# ShiftRegisters.net
KiCad netlist of a schematic drawn in Altium Designer
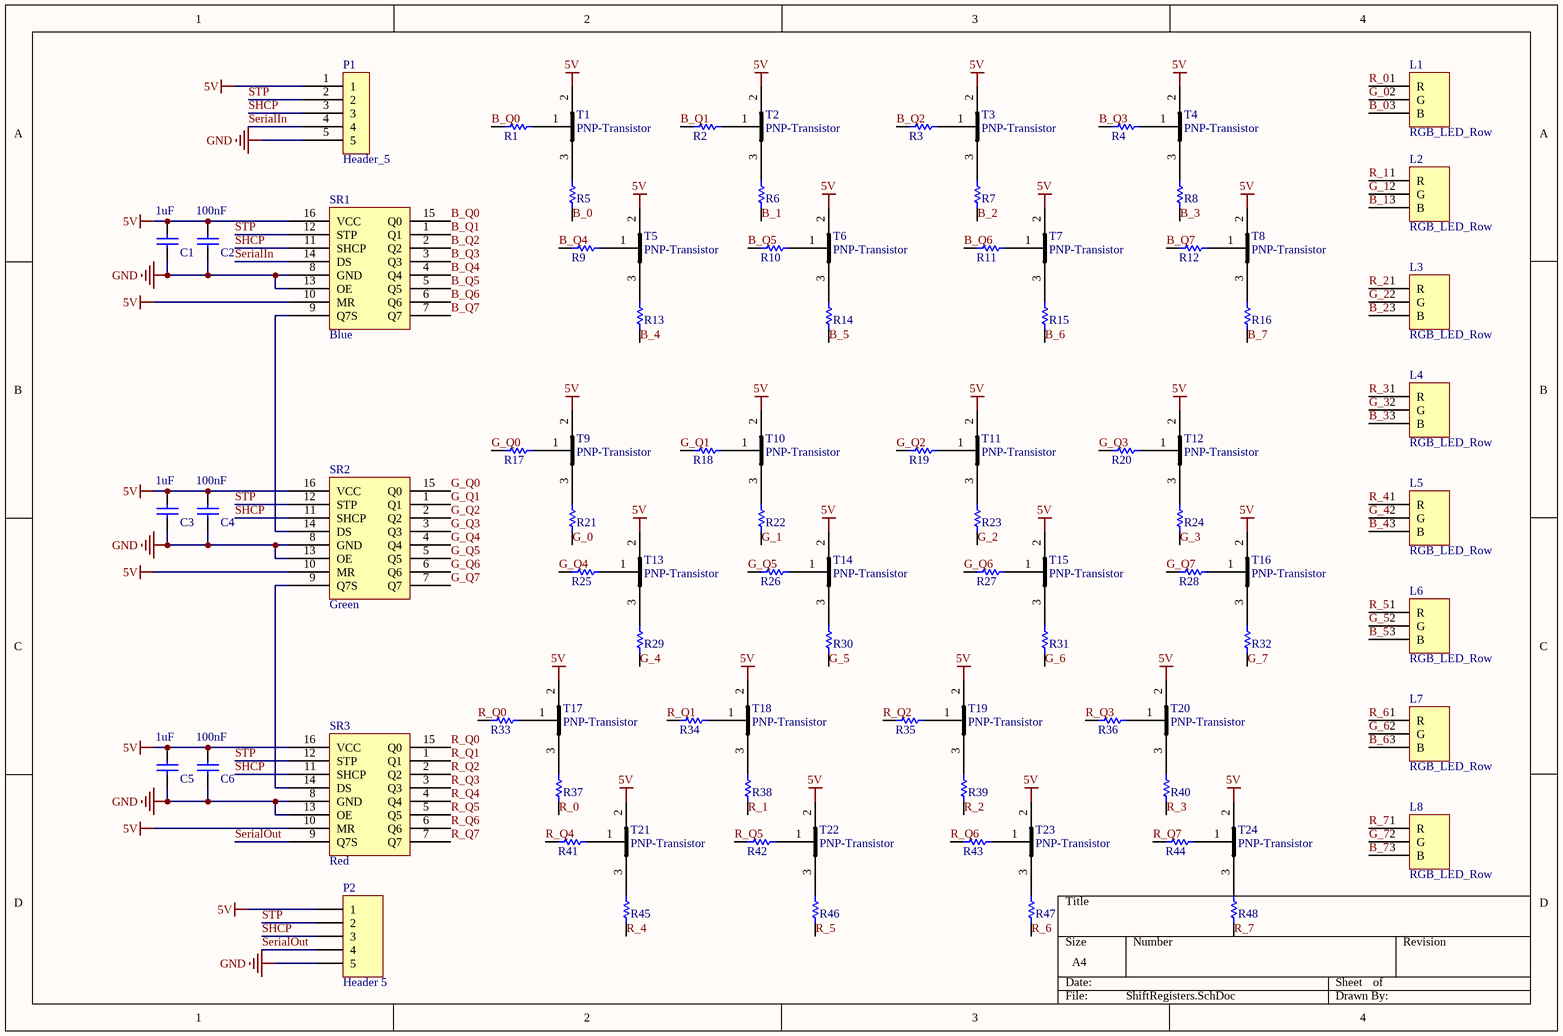
[diagram p0: ShiftRegisters.SchDoc]

(export (version "E")
  (design (tool "Eeschema 10.0.6"))
  (components
    (comp (ref "C1")
      (value "1uF")
      (footprint "CAPC1206(3216)190_L")
      (description "CAP 100nF 16V Â±1% 1206 (3216 Metric) Thickness 1.9mm SMD")
      (fields (field (name "TOLERANCE") "Â±1%") (field (name "Comment") "CAP 100nF 16V 1206(3216)"))
      (libsource (lib "Altium Content Vault") (part "CAP"))
    )
    (comp (ref "C2")
      (value "100nF")
      (footprint "CAPC1206(3216)190_L")
      (description "CAP 100nF 16V Â±1% 1206 (3216 Metric) Thickness 1.9mm SMD")
      (fields (field (name "TOLERANCE") "Â±1%") (field (name "Comment") "CAP 100nF 16V 1206(3216)"))
      (libsource (lib "Altium Content Vault") (part "CAP"))
    )
    (comp (ref "C3")
      (value "1uF")
      (footprint "CAPC1206(3216)190_L")
      (description "CAP 100nF 16V Â±1% 1206 (3216 Metric) Thickness 1.9mm SMD")
      (fields (field (name "TOLERANCE") "Â±1%") (field (name "Comment") "CAP 100nF 16V 1206(3216)"))
      (libsource (lib "Altium Content Vault") (part "CAP"))
    )
    (comp (ref "C4")
      (value "100nF")
      (footprint "CAPC1206(3216)190_L")
      (description "CAP 100nF 16V Â±1% 1206 (3216 Metric) Thickness 1.9mm SMD")
      (fields (field (name "TOLERANCE") "Â±1%") (field (name "Comment") "CAP 100nF 16V 1206(3216)"))
      (libsource (lib "Altium Content Vault") (part "CAP"))
    )
    (comp (ref "C5")
      (value "1uF")
      (footprint "CAPC1206(3216)190_L")
      (description "CAP 100nF 16V Â±1% 1206 (3216 Metric) Thickness 1.9mm SMD")
      (fields (field (name "TOLERANCE") "Â±1%") (field (name "Comment") "CAP 100nF 16V 1206(3216)"))
      (libsource (lib "Altium Content Vault") (part "CAP"))
    )
    (comp (ref "C6")
      (value "100nF")
      (footprint "CAPC1206(3216)190_L")
      (description "CAP 100nF 16V Â±1% 1206 (3216 Metric) Thickness 1.9mm SMD")
      (fields (field (name "TOLERANCE") "Â±1%") (field (name "Comment") "CAP 100nF 16V 1206(3216)"))
      (libsource (lib "Altium Content Vault") (part "CAP"))
    )
    (comp (ref "L1")
      (value "RGB_LED_Row")
      (footprint "LED_Row")
      (libsource (lib "RGB-Cube") (part "RGB_LED_Row"))
    )
    (comp (ref "L2")
      (value "RGB_LED_Row")
      (footprint "LED_Row")
      (libsource (lib "RGB-Cube") (part "RGB_LED_Row"))
    )
    (comp (ref "L3")
      (value "RGB_LED_Row")
      (footprint "LED_Row")
      (libsource (lib "RGB-Cube") (part "RGB_LED_Row"))
    )
    (comp (ref "L4")
      (value "RGB_LED_Row")
      (footprint "LED_Row")
      (libsource (lib "RGB-Cube") (part "RGB_LED_Row"))
    )
    (comp (ref "L5")
      (value "RGB_LED_Row")
      (footprint "LED_Row")
      (libsource (lib "RGB-Cube") (part "RGB_LED_Row"))
    )
    (comp (ref "L6")
      (value "RGB_LED_Row")
      (footprint "LED_Row")
      (libsource (lib "RGB-Cube") (part "RGB_LED_Row"))
    )
    (comp (ref "L7")
      (value "RGB_LED_Row")
      (footprint "LED_Row")
      (libsource (lib "RGB-Cube") (part "RGB_LED_Row"))
    )
    (comp (ref "L8")
      (value "RGB_LED_Row")
      (footprint "LED_Row")
      (libsource (lib "RGB-Cube") (part "RGB_LED_Row"))
    )
    (comp (ref "P1")
      (value "Header_5")
      (footprint "PinHeader")
      (libsource (lib "RGB-Cube") (part "Header_5"))
    )
    (comp (ref "P2")
      (value "Header 5")
      (footprint "HDR1X5")
      (description "Header, 5-Pin")
      (fields (field (name "PUBLISHER") "Altium Limited"))
      (libsource (lib "Miscellaneous Connectors") (part "Header 5"))
    )
    (comp (ref "R1")
      (value "43k 5% 1206(3216)")
      (footprint "RESC1206(3216)_M")
      (description "43k 0.25W 5% 1206 (3216 Metric)  SMD")
      (fields (field (name "TOLERANCE") "5 %") (field (name "POWER") "0.25 W"))
      (libsource (lib "Altium Content Vault") (part "CMP-1014-00009-1"))
    )
    (comp (ref "R2")
      (value "43k 5% 1206(3216)")
      (footprint "RESC1206(3216)_M")
      (description "43k 0.25W 5% 1206 (3216 Metric)  SMD")
      (fields (field (name "TOLERANCE") "5 %") (field (name "POWER") "0.25 W"))
      (libsource (lib "Altium Content Vault") (part "CMP-1014-00009-1"))
    )
    (comp (ref "R3")
      (value "43k 5% 1206(3216)")
      (footprint "RESC1206(3216)_M")
      (description "43k 0.25W 5% 1206 (3216 Metric)  SMD")
      (fields (field (name "TOLERANCE") "5 %") (field (name "POWER") "0.25 W"))
      (libsource (lib "Altium Content Vault") (part "CMP-1014-00009-1"))
    )
    (comp (ref "R4")
      (value "43k 5% 1206(3216)")
      (footprint "RESC1206(3216)_M")
      (description "43k 0.25W 5% 1206 (3216 Metric)  SMD")
      (fields (field (name "TOLERANCE") "5 %") (field (name "POWER") "0.25 W"))
      (libsource (lib "Altium Content Vault") (part "CMP-1014-00009-1"))
    )
    (comp (ref "R5")
      (value "2R 5% 1206(3216)")
      (footprint "RESC1206(3216)_M")
      (description "2R 0.25W 5% 1206 (3216 Metric)  SMD")
      (fields (field (name "TOLERANCE") "5 %") (field (name "POWER") "0.25 W"))
      (libsource (lib "Altium Content Vault") (part "CMP-1014-00009-1"))
    )
    (comp (ref "R6")
      (value "2R 5% 1206(3216)")
      (footprint "RESC1206(3216)_M")
      (description "2R 0.25W 5% 1206 (3216 Metric)  SMD")
      (fields (field (name "TOLERANCE") "5 %") (field (name "POWER") "0.25 W"))
      (libsource (lib "Altium Content Vault") (part "CMP-1014-00009-1"))
    )
    (comp (ref "R7")
      (value "2R 5% 1206(3216)")
      (footprint "RESC1206(3216)_M")
      (description "2R 0.25W 5% 1206 (3216 Metric)  SMD")
      (fields (field (name "TOLERANCE") "5 %") (field (name "POWER") "0.25 W"))
      (libsource (lib "Altium Content Vault") (part "CMP-1014-00009-1"))
    )
    (comp (ref "R8")
      (value "2R 5% 1206(3216)")
      (footprint "RESC1206(3216)_M")
      (description "2R 0.25W 5% 1206 (3216 Metric)  SMD")
      (fields (field (name "TOLERANCE") "5 %") (field (name "POWER") "0.25 W"))
      (libsource (lib "Altium Content Vault") (part "CMP-1014-00009-1"))
    )
    (comp (ref "R9")
      (value "43k 5% 1206(3216)")
      (footprint "RESC1206(3216)_M")
      (description "43k 0.25W 5% 1206 (3216 Metric)  SMD")
      (fields (field (name "TOLERANCE") "5 %") (field (name "POWER") "0.25 W"))
      (libsource (lib "Altium Content Vault") (part "CMP-1014-00009-1"))
    )
    (comp (ref "R10")
      (value "43k 5% 1206(3216)")
      (footprint "RESC1206(3216)_M")
      (description "43k 0.25W 5% 1206 (3216 Metric)  SMD")
      (fields (field (name "TOLERANCE") "5 %") (field (name "POWER") "0.25 W"))
      (libsource (lib "Altium Content Vault") (part "CMP-1014-00009-1"))
    )
    (comp (ref "R11")
      (value "43k 5% 1206(3216)")
      (footprint "RESC1206(3216)_M")
      (description "43k 0.25W 5% 1206 (3216 Metric)  SMD")
      (fields (field (name "TOLERANCE") "5 %") (field (name "POWER") "0.25 W"))
      (libsource (lib "Altium Content Vault") (part "CMP-1014-00009-1"))
    )
    (comp (ref "R12")
      (value "43k 5% 1206(3216)")
      (footprint "RESC1206(3216)_M")
      (description "43k 0.25W 5% 1206 (3216 Metric)  SMD")
      (fields (field (name "TOLERANCE") "5 %") (field (name "POWER") "0.25 W"))
      (libsource (lib "Altium Content Vault") (part "CMP-1014-00009-1"))
    )
    (comp (ref "R13")
      (value "2R 5% 1206(3216)")
      (footprint "RESC1206(3216)_M")
      (description "2R 0.25W 5% 1206 (3216 Metric)  SMD")
      (fields (field (name "TOLERANCE") "5 %") (field (name "POWER") "0.25 W"))
      (libsource (lib "Altium Content Vault") (part "CMP-1014-00009-1"))
    )
    (comp (ref "R14")
      (value "2R 5% 1206(3216)")
      (footprint "RESC1206(3216)_M")
      (description "2R 0.25W 5% 1206 (3216 Metric)  SMD")
      (fields (field (name "TOLERANCE") "5 %") (field (name "POWER") "0.25 W"))
      (libsource (lib "Altium Content Vault") (part "CMP-1014-00009-1"))
    )
    (comp (ref "R15")
      (value "2R 5% 1206(3216)")
      (footprint "RESC1206(3216)_M")
      (description "2R 0.25W 5% 1206 (3216 Metric)  SMD")
      (fields (field (name "TOLERANCE") "5 %") (field (name "POWER") "0.25 W"))
      (libsource (lib "Altium Content Vault") (part "CMP-1014-00009-1"))
    )
    (comp (ref "R16")
      (value "2R 5% 1206(3216)")
      (footprint "RESC1206(3216)_M")
      (description "2R 0.25W 5% 1206 (3216 Metric)  SMD")
      (fields (field (name "TOLERANCE") "5 %") (field (name "POWER") "0.25 W"))
      (libsource (lib "Altium Content Vault") (part "CMP-1014-00009-1"))
    )
    (comp (ref "R17")
      (value "43k 5% 1206(3216)")
      (footprint "RESC1206(3216)_M")
      (description "43k 0.25W 5% 1206 (3216 Metric)  SMD")
      (fields (field (name "TOLERANCE") "5 %") (field (name "POWER") "0.25 W"))
      (libsource (lib "Altium Content Vault") (part "CMP-1014-00009-1"))
    )
    (comp (ref "R18")
      (value "43k 5% 1206(3216)")
      (footprint "RESC1206(3216)_M")
      (description "43k 0.25W 5% 1206 (3216 Metric)  SMD")
      (fields (field (name "TOLERANCE") "5 %") (field (name "POWER") "0.25 W"))
      (libsource (lib "Altium Content Vault") (part "CMP-1014-00009-1"))
    )
    (comp (ref "R19")
      (value "43k 5% 1206(3216)")
      (footprint "RESC1206(3216)_M")
      (description "43k 0.25W 5% 1206 (3216 Metric)  SMD")
      (fields (field (name "TOLERANCE") "5 %") (field (name "POWER") "0.25 W"))
      (libsource (lib "Altium Content Vault") (part "CMP-1014-00009-1"))
    )
    (comp (ref "R20")
      (value "43k 5% 1206(3216)")
      (footprint "RESC1206(3216)_M")
      (description "43k 0.25W 5% 1206 (3216 Metric)  SMD")
      (fields (field (name "TOLERANCE") "5 %") (field (name "POWER") "0.25 W"))
      (libsource (lib "Altium Content Vault") (part "CMP-1014-00009-1"))
    )
    (comp (ref "R21")
      (value "2R 5% 1206(3216)")
      (footprint "RESC1206(3216)_M")
      (description "2R 0.25W 5% 1206 (3216 Metric)  SMD")
      (fields (field (name "TOLERANCE") "5 %") (field (name "POWER") "0.25 W"))
      (libsource (lib "Altium Content Vault") (part "CMP-1014-00009-1"))
    )
    (comp (ref "R22")
      (value "2R 5% 1206(3216)")
      (footprint "RESC1206(3216)_M")
      (description "2R 0.25W 5% 1206 (3216 Metric)  SMD")
      (fields (field (name "TOLERANCE") "5 %") (field (name "POWER") "0.25 W"))
      (libsource (lib "Altium Content Vault") (part "CMP-1014-00009-1"))
    )
    (comp (ref "R23")
      (value "2R 5% 1206(3216)")
      (footprint "RESC1206(3216)_M")
      (description "2R 0.25W 5% 1206 (3216 Metric)  SMD")
      (fields (field (name "TOLERANCE") "5 %") (field (name "POWER") "0.25 W"))
      (libsource (lib "Altium Content Vault") (part "CMP-1014-00009-1"))
    )
    (comp (ref "R24")
      (value "2R 5% 1206(3216)")
      (footprint "RESC1206(3216)_M")
      (description "2R 0.25W 5% 1206 (3216 Metric)  SMD")
      (fields (field (name "TOLERANCE") "5 %") (field (name "POWER") "0.25 W"))
      (libsource (lib "Altium Content Vault") (part "CMP-1014-00009-1"))
    )
    (comp (ref "R25")
      (value "43k 5% 1206(3216)")
      (footprint "RESC1206(3216)_M")
      (description "43k 0.25W 5% 1206 (3216 Metric)  SMD")
      (fields (field (name "TOLERANCE") "5 %") (field (name "POWER") "0.25 W"))
      (libsource (lib "Altium Content Vault") (part "CMP-1014-00009-1"))
    )
    (comp (ref "R26")
      (value "43k 5% 1206(3216)")
      (footprint "RESC1206(3216)_M")
      (description "43k 0.25W 5% 1206 (3216 Metric)  SMD")
      (fields (field (name "TOLERANCE") "5 %") (field (name "POWER") "0.25 W"))
      (libsource (lib "Altium Content Vault") (part "CMP-1014-00009-1"))
    )
    (comp (ref "R27")
      (value "43k 5% 1206(3216)")
      (footprint "RESC1206(3216)_M")
      (description "43k 0.25W 5% 1206 (3216 Metric)  SMD")
      (fields (field (name "TOLERANCE") "5 %") (field (name "POWER") "0.25 W"))
      (libsource (lib "Altium Content Vault") (part "CMP-1014-00009-1"))
    )
    (comp (ref "R28")
      (value "43k 5% 1206(3216)")
      (footprint "RESC1206(3216)_M")
      (description "43k 0.25W 5% 1206 (3216 Metric)  SMD")
      (fields (field (name "TOLERANCE") "5 %") (field (name "POWER") "0.25 W"))
      (libsource (lib "Altium Content Vault") (part "CMP-1014-00009-1"))
    )
    (comp (ref "R29")
      (value "2R 5% 1206(3216)")
      (footprint "RESC1206(3216)_M")
      (description "2R 0.25W 5% 1206 (3216 Metric)  SMD")
      (fields (field (name "TOLERANCE") "5 %") (field (name "POWER") "0.25 W"))
      (libsource (lib "Altium Content Vault") (part "CMP-1014-00009-1"))
    )
    (comp (ref "R30")
      (value "2R 5% 1206(3216)")
      (footprint "RESC1206(3216)_M")
      (description "2R 0.25W 5% 1206 (3216 Metric)  SMD")
      (fields (field (name "TOLERANCE") "5 %") (field (name "POWER") "0.25 W"))
      (libsource (lib "Altium Content Vault") (part "CMP-1014-00009-1"))
    )
    (comp (ref "R31")
      (value "2R 5% 1206(3216)")
      (footprint "RESC1206(3216)_M")
      (description "2R 0.25W 5% 1206 (3216 Metric)  SMD")
      (fields (field (name "TOLERANCE") "5 %") (field (name "POWER") "0.25 W"))
      (libsource (lib "Altium Content Vault") (part "CMP-1014-00009-1"))
    )
    (comp (ref "R32")
      (value "2R 5% 1206(3216)")
      (footprint "RESC1206(3216)_M")
      (description "2R 0.25W 5% 1206 (3216 Metric)  SMD")
      (fields (field (name "TOLERANCE") "5 %") (field (name "POWER") "0.25 W"))
      (libsource (lib "Altium Content Vault") (part "CMP-1014-00009-1"))
    )
    (comp (ref "R33")
      (value "43k 5% 1206(3216)")
      (footprint "RESC1206(3216)_M")
      (description "43k 0.25W 5% 1206 (3216 Metric)  SMD")
      (fields (field (name "TOLERANCE") "5 %") (field (name "POWER") "0.25 W"))
      (libsource (lib "Altium Content Vault") (part "CMP-1014-00009-1"))
    )
    (comp (ref "R34")
      (value "43k 5% 1206(3216)")
      (footprint "RESC1206(3216)_M")
      (description "43k 0.25W 5% 1206 (3216 Metric)  SMD")
      (fields (field (name "TOLERANCE") "5 %") (field (name "POWER") "0.25 W"))
      (libsource (lib "Altium Content Vault") (part "CMP-1014-00009-1"))
    )
    (comp (ref "R35")
      (value "43k 5% 1206(3216)")
      (footprint "RESC1206(3216)_M")
      (description "43k 0.25W 5% 1206 (3216 Metric)  SMD")
      (fields (field (name "TOLERANCE") "5 %") (field (name "POWER") "0.25 W"))
      (libsource (lib "Altium Content Vault") (part "CMP-1014-00009-1"))
    )
    (comp (ref "R36")
      (value "43k 5% 1206(3216)")
      (footprint "RESC1206(3216)_M")
      (description "43k 0.25W 5% 1206 (3216 Metric)  SMD")
      (fields (field (name "TOLERANCE") "5 %") (field (name "POWER") "0.25 W"))
      (libsource (lib "Altium Content Vault") (part "CMP-1014-00009-1"))
    )
    (comp (ref "R37")
      (value "2R 5% 1206(3216)")
      (footprint "RESC1206(3216)_M")
      (description "2R 0.25W 5% 1206 (3216 Metric)  SMD")
      (fields (field (name "TOLERANCE") "5 %") (field (name "POWER") "0.25 W"))
      (libsource (lib "Altium Content Vault") (part "CMP-1014-00009-1"))
    )
    (comp (ref "R38")
      (value "2R 5% 1206(3216)")
      (footprint "RESC1206(3216)_M")
      (description "2R 0.25W 5% 1206 (3216 Metric)  SMD")
      (fields (field (name "TOLERANCE") "5 %") (field (name "POWER") "0.25 W"))
      (libsource (lib "Altium Content Vault") (part "CMP-1014-00009-1"))
    )
    (comp (ref "R39")
      (value "2R 5% 1206(3216)")
      (footprint "RESC1206(3216)_M")
      (description "2R 0.25W 5% 1206 (3216 Metric)  SMD")
      (fields (field (name "TOLERANCE") "5 %") (field (name "POWER") "0.25 W"))
      (libsource (lib "Altium Content Vault") (part "CMP-1014-00009-1"))
    )
    (comp (ref "R40")
      (value "2R 5% 1206(3216)")
      (footprint "RESC1206(3216)_M")
      (description "2R 0.25W 5% 1206 (3216 Metric)  SMD")
      (fields (field (name "TOLERANCE") "5 %") (field (name "POWER") "0.25 W"))
      (libsource (lib "Altium Content Vault") (part "CMP-1014-00009-1"))
    )
    (comp (ref "R41")
      (value "43k 5% 1206(3216)")
      (footprint "RESC1206(3216)_M")
      (description "43k 0.25W 5% 1206 (3216 Metric)  SMD")
      (fields (field (name "TOLERANCE") "5 %") (field (name "POWER") "0.25 W"))
      (libsource (lib "Altium Content Vault") (part "CMP-1014-00009-1"))
    )
    (comp (ref "R42")
      (value "43k 5% 1206(3216)")
      (footprint "RESC1206(3216)_M")
      (description "43k 0.25W 5% 1206 (3216 Metric)  SMD")
      (fields (field (name "TOLERANCE") "5 %") (field (name "POWER") "0.25 W"))
      (libsource (lib "Altium Content Vault") (part "CMP-1014-00009-1"))
    )
    (comp (ref "R43")
      (value "43k 5% 1206(3216)")
      (footprint "RESC1206(3216)_M")
      (description "43k 0.25W 5% 1206 (3216 Metric)  SMD")
      (fields (field (name "TOLERANCE") "5 %") (field (name "POWER") "0.25 W"))
      (libsource (lib "Altium Content Vault") (part "CMP-1014-00009-1"))
    )
    (comp (ref "R44")
      (value "43k 5% 1206(3216)")
      (footprint "RESC1206(3216)_M")
      (description "43k 0.25W 5% 1206 (3216 Metric)  SMD")
      (fields (field (name "TOLERANCE") "5 %") (field (name "POWER") "0.25 W"))
      (libsource (lib "Altium Content Vault") (part "CMP-1014-00009-1"))
    )
    (comp (ref "R45")
      (value "2R 5% 1206(3216)")
      (footprint "RESC1206(3216)_M")
      (description "2R 0.25W 5% 1206 (3216 Metric)  SMD")
      (fields (field (name "TOLERANCE") "5 %") (field (name "POWER") "0.25 W"))
      (libsource (lib "Altium Content Vault") (part "CMP-1014-00009-1"))
    )
    (comp (ref "R46")
      (value "2R 5% 1206(3216)")
      (footprint "RESC1206(3216)_M")
      (description "2R 0.25W 5% 1206 (3216 Metric)  SMD")
      (fields (field (name "TOLERANCE") "5 %") (field (name "POWER") "0.25 W"))
      (libsource (lib "Altium Content Vault") (part "CMP-1014-00009-1"))
    )
    (comp (ref "R47")
      (value "2R 5% 1206(3216)")
      (footprint "RESC1206(3216)_M")
      (description "2R 0.25W 5% 1206 (3216 Metric)  SMD")
      (fields (field (name "TOLERANCE") "5 %") (field (name "POWER") "0.25 W"))
      (libsource (lib "Altium Content Vault") (part "CMP-1014-00009-1"))
    )
    (comp (ref "R48")
      (value "2R 5% 1206(3216)")
      (footprint "RESC1206(3216)_M")
      (description "2R 0.25W 5% 1206 (3216 Metric)  SMD")
      (fields (field (name "TOLERANCE") "5 %") (field (name "POWER") "0.25 W"))
      (libsource (lib "Altium Content Vault") (part "CMP-1014-00009-1"))
    )
    (comp (ref "SR1")
      (value "Blue")
      (footprint "SOP16")
      (description "74HC595 Farnell:  2098004")
      (libsource (lib "RGB-Cube") (part "74HC595"))
    )
    (comp (ref "SR2")
      (value "Green")
      (footprint "SOP16")
      (description "74HC595 Farnell:  2098004")
      (libsource (lib "RGB-Cube") (part "74HC595"))
    )
    (comp (ref "SR3")
      (value "Red")
      (footprint "SOP16")
      (description "74HC595 Farnell:  2098004")
      (libsource (lib "RGB-Cube") (part "74HC595"))
    )
    (comp (ref "T1")
      (value "PNP-Transistor")
      (footprint "SOT-223")
      (description "Reichelt: BCP 51-16 NXP")
      (libsource (lib "RGB-Cube") (part "PNP-Transistor"))
    )
    (comp (ref "T2")
      (value "PNP-Transistor")
      (footprint "SOT-223")
      (description "Reichelt: BCP 51-16 NXP")
      (libsource (lib "RGB-Cube") (part "PNP-Transistor"))
    )
    (comp (ref "T3")
      (value "PNP-Transistor")
      (footprint "SOT-223")
      (description "Reichelt: BCP 51-16 NXP")
      (libsource (lib "RGB-Cube") (part "PNP-Transistor"))
    )
    (comp (ref "T4")
      (value "PNP-Transistor")
      (footprint "SOT-223")
      (description "Reichelt: BCP 51-16 NXP")
      (libsource (lib "RGB-Cube") (part "PNP-Transistor"))
    )
    (comp (ref "T5")
      (value "PNP-Transistor")
      (footprint "SOT-223")
      (description "Reichelt: BCP 51-16 NXP")
      (libsource (lib "RGB-Cube") (part "PNP-Transistor"))
    )
    (comp (ref "T6")
      (value "PNP-Transistor")
      (footprint "SOT-223")
      (description "Reichelt: BCP 51-16 NXP")
      (libsource (lib "RGB-Cube") (part "PNP-Transistor"))
    )
    (comp (ref "T7")
      (value "PNP-Transistor")
      (footprint "SOT-223")
      (description "Reichelt: BCP 51-16 NXP")
      (libsource (lib "RGB-Cube") (part "PNP-Transistor"))
    )
    (comp (ref "T8")
      (value "PNP-Transistor")
      (footprint "SOT-223")
      (description "Reichelt: BCP 51-16 NXP")
      (libsource (lib "RGB-Cube") (part "PNP-Transistor"))
    )
    (comp (ref "T9")
      (value "PNP-Transistor")
      (footprint "SOT-223")
      (description "Reichelt: BCP 51-16 NXP")
      (libsource (lib "RGB-Cube") (part "PNP-Transistor"))
    )
    (comp (ref "T10")
      (value "PNP-Transistor")
      (footprint "SOT-223")
      (description "Reichelt: BCP 51-16 NXP")
      (libsource (lib "RGB-Cube") (part "PNP-Transistor"))
    )
    (comp (ref "T11")
      (value "PNP-Transistor")
      (footprint "SOT-223")
      (description "Reichelt: BCP 51-16 NXP")
      (libsource (lib "RGB-Cube") (part "PNP-Transistor"))
    )
    (comp (ref "T12")
      (value "PNP-Transistor")
      (footprint "SOT-223")
      (description "Reichelt: BCP 51-16 NXP")
      (libsource (lib "RGB-Cube") (part "PNP-Transistor"))
    )
    (comp (ref "T13")
      (value "PNP-Transistor")
      (footprint "SOT-223")
      (description "Reichelt: BCP 51-16 NXP")
      (libsource (lib "RGB-Cube") (part "PNP-Transistor"))
    )
    (comp (ref "T14")
      (value "PNP-Transistor")
      (footprint "SOT-223")
      (description "Reichelt: BCP 51-16 NXP")
      (libsource (lib "RGB-Cube") (part "PNP-Transistor"))
    )
    (comp (ref "T15")
      (value "PNP-Transistor")
      (footprint "SOT-223")
      (description "Reichelt: BCP 51-16 NXP")
      (libsource (lib "RGB-Cube") (part "PNP-Transistor"))
    )
    (comp (ref "T16")
      (value "PNP-Transistor")
      (footprint "SOT-223")
      (description "Reichelt: BCP 51-16 NXP")
      (libsource (lib "RGB-Cube") (part "PNP-Transistor"))
    )
    (comp (ref "T17")
      (value "PNP-Transistor")
      (footprint "SOT-223")
      (description "Reichelt: BCP 51-16 NXP")
      (libsource (lib "RGB-Cube") (part "PNP-Transistor"))
    )
    (comp (ref "T18")
      (value "PNP-Transistor")
      (footprint "SOT-223")
      (description "Reichelt: BCP 51-16 NXP")
      (libsource (lib "RGB-Cube") (part "PNP-Transistor"))
    )
    (comp (ref "T19")
      (value "PNP-Transistor")
      (footprint "SOT-223")
      (description "Reichelt: BCP 51-16 NXP")
      (libsource (lib "RGB-Cube") (part "PNP-Transistor"))
    )
    (comp (ref "T20")
      (value "PNP-Transistor")
      (footprint "SOT-223")
      (description "Reichelt: BCP 51-16 NXP")
      (libsource (lib "RGB-Cube") (part "PNP-Transistor"))
    )
    (comp (ref "T21")
      (value "PNP-Transistor")
      (footprint "SOT-223")
      (description "Reichelt: BCP 51-16 NXP")
      (libsource (lib "RGB-Cube") (part "PNP-Transistor"))
    )
    (comp (ref "T22")
      (value "PNP-Transistor")
      (footprint "SOT-223")
      (description "Reichelt: BCP 51-16 NXP")
      (libsource (lib "RGB-Cube") (part "PNP-Transistor"))
    )
    (comp (ref "T23")
      (value "PNP-Transistor")
      (footprint "SOT-223")
      (description "Reichelt: BCP 51-16 NXP")
      (libsource (lib "RGB-Cube") (part "PNP-Transistor"))
    )
    (comp (ref "T24")
      (value "PNP-Transistor")
      (footprint "SOT-223")
      (description "Reichelt: BCP 51-16 NXP")
      (libsource (lib "RGB-Cube") (part "PNP-Transistor"))
    )
  )
  (nets
    (net (code "2") (name "/B_0") (class "Default")
      (node (ref "L1") (pin "3") (pinfunction "B_3") (pintype "passive"))
      (node (ref "R5") (pin "1") (pinfunction "1_1") (pintype "passive"))
    )
    (net (code "3") (name "/B_1") (class "Default")
      (node (ref "L2") (pin "3") (pinfunction "B_3") (pintype "passive"))
      (node (ref "R6") (pin "1") (pinfunction "1_1") (pintype "passive"))
    )
    (net (code "4") (name "/B_2") (class "Default")
      (node (ref "L3") (pin "3") (pinfunction "B_3") (pintype "passive"))
      (node (ref "R7") (pin "1") (pinfunction "1_1") (pintype "passive"))
    )
    (net (code "5") (name "/B_3") (class "Default")
      (node (ref "L4") (pin "3") (pinfunction "B_3") (pintype "passive"))
      (node (ref "R8") (pin "1") (pinfunction "1_1") (pintype "passive"))
    )
    (net (code "6") (name "/B_4") (class "Default")
      (node (ref "L5") (pin "3") (pinfunction "B_3") (pintype "passive"))
      (node (ref "R13") (pin "1") (pinfunction "1_1") (pintype "passive"))
    )
    (net (code "7") (name "/B_5") (class "Default")
      (node (ref "L6") (pin "3") (pinfunction "B_3") (pintype "passive"))
      (node (ref "R14") (pin "1") (pinfunction "1_1") (pintype "passive"))
    )
    (net (code "8") (name "/B_6") (class "Default")
      (node (ref "L7") (pin "3") (pinfunction "B_3") (pintype "passive"))
      (node (ref "R15") (pin "1") (pinfunction "1_1") (pintype "passive"))
    )
    (net (code "9") (name "/B_7") (class "Default")
      (node (ref "L8") (pin "3") (pinfunction "B_3") (pintype "passive"))
      (node (ref "R16") (pin "1") (pinfunction "1_1") (pintype "passive"))
    )
    (net (code "10") (name "/B_Q0") (class "Default")
      (node (ref "R1") (pin "1") (pinfunction "1_1") (pintype "passive"))
      (node (ref "SR1") (pin "15") (pinfunction "Q0_15") (pintype "passive"))
    )
    (net (code "11") (name "/B_Q1") (class "Default")
      (node (ref "R2") (pin "1") (pinfunction "1_1") (pintype "passive"))
      (node (ref "SR1") (pin "1") (pinfunction "Q1_1") (pintype "passive"))
    )
    (net (code "12") (name "/B_Q2") (class "Default")
      (node (ref "R3") (pin "1") (pinfunction "1_1") (pintype "passive"))
      (node (ref "SR1") (pin "2") (pinfunction "Q2_2") (pintype "passive"))
    )
    (net (code "13") (name "/B_Q3") (class "Default")
      (node (ref "R4") (pin "1") (pinfunction "1_1") (pintype "passive"))
      (node (ref "SR1") (pin "3") (pinfunction "Q3_3") (pintype "passive"))
    )
    (net (code "14") (name "/B_Q4") (class "Default")
      (node (ref "R9") (pin "1") (pinfunction "1_1") (pintype "passive"))
      (node (ref "SR1") (pin "4") (pinfunction "Q4_4") (pintype "passive"))
    )
    (net (code "15") (name "/B_Q5") (class "Default")
      (node (ref "R10") (pin "1") (pinfunction "1_1") (pintype "passive"))
      (node (ref "SR1") (pin "5") (pinfunction "Q5_5") (pintype "passive"))
    )
    (net (code "16") (name "/B_Q6") (class "Default")
      (node (ref "R11") (pin "1") (pinfunction "1_1") (pintype "passive"))
      (node (ref "SR1") (pin "6") (pinfunction "Q6_6") (pintype "passive"))
    )
    (net (code "17") (name "/B_Q7") (class "Default")
      (node (ref "R12") (pin "1") (pinfunction "1_1") (pintype "passive"))
      (node (ref "SR1") (pin "7") (pinfunction "Q7_7") (pintype "passive"))
    )
    (net (code "18") (name "/G_0") (class "Default")
      (node (ref "L1") (pin "2") (pinfunction "G_2") (pintype "passive"))
      (node (ref "R21") (pin "1") (pinfunction "1_1") (pintype "passive"))
    )
    (net (code "19") (name "/G_1") (class "Default")
      (node (ref "L2") (pin "2") (pinfunction "G_2") (pintype "passive"))
      (node (ref "R22") (pin "1") (pinfunction "1_1") (pintype "passive"))
    )
    (net (code "20") (name "/G_2") (class "Default")
      (node (ref "L3") (pin "2") (pinfunction "G_2") (pintype "passive"))
      (node (ref "R23") (pin "1") (pinfunction "1_1") (pintype "passive"))
    )
    (net (code "21") (name "/G_3") (class "Default")
      (node (ref "L4") (pin "2") (pinfunction "G_2") (pintype "passive"))
      (node (ref "R24") (pin "1") (pinfunction "1_1") (pintype "passive"))
    )
    (net (code "22") (name "/G_4") (class "Default")
      (node (ref "L5") (pin "2") (pinfunction "G_2") (pintype "passive"))
      (node (ref "R29") (pin "1") (pinfunction "1_1") (pintype "passive"))
    )
    (net (code "23") (name "/G_5") (class "Default")
      (node (ref "L6") (pin "2") (pinfunction "G_2") (pintype "passive"))
      (node (ref "R30") (pin "1") (pinfunction "1_1") (pintype "passive"))
    )
    (net (code "24") (name "/G_6") (class "Default")
      (node (ref "L7") (pin "2") (pinfunction "G_2") (pintype "passive"))
      (node (ref "R31") (pin "1") (pinfunction "1_1") (pintype "passive"))
    )
    (net (code "25") (name "/G_7") (class "Default")
      (node (ref "L8") (pin "2") (pinfunction "G_2") (pintype "passive"))
      (node (ref "R32") (pin "1") (pinfunction "1_1") (pintype "passive"))
    )
    (net (code "26") (name "/G_Q0") (class "Default")
      (node (ref "R17") (pin "1") (pinfunction "1_1") (pintype "passive"))
      (node (ref "SR2") (pin "15") (pinfunction "Q0_15") (pintype "passive"))
    )
    (net (code "27") (name "/G_Q1") (class "Default")
      (node (ref "R18") (pin "1") (pinfunction "1_1") (pintype "passive"))
      (node (ref "SR2") (pin "1") (pinfunction "Q1_1") (pintype "passive"))
    )
    (net (code "28") (name "/G_Q2") (class "Default")
      (node (ref "R19") (pin "1") (pinfunction "1_1") (pintype "passive"))
      (node (ref "SR2") (pin "2") (pinfunction "Q2_2") (pintype "passive"))
    )
    (net (code "29") (name "/G_Q3") (class "Default")
      (node (ref "R20") (pin "1") (pinfunction "1_1") (pintype "passive"))
      (node (ref "SR2") (pin "3") (pinfunction "Q3_3") (pintype "passive"))
    )
    (net (code "30") (name "/G_Q4") (class "Default")
      (node (ref "R25") (pin "1") (pinfunction "1_1") (pintype "passive"))
      (node (ref "SR2") (pin "4") (pinfunction "Q4_4") (pintype "passive"))
    )
    (net (code "31") (name "/G_Q5") (class "Default")
      (node (ref "R26") (pin "1") (pinfunction "1_1") (pintype "passive"))
      (node (ref "SR2") (pin "5") (pinfunction "Q5_5") (pintype "passive"))
    )
    (net (code "32") (name "/G_Q6") (class "Default")
      (node (ref "R27") (pin "1") (pinfunction "1_1") (pintype "passive"))
      (node (ref "SR2") (pin "6") (pinfunction "Q6_6") (pintype "passive"))
    )
    (net (code "33") (name "/G_Q7") (class "Default")
      (node (ref "R28") (pin "1") (pinfunction "1_1") (pintype "passive"))
      (node (ref "SR2") (pin "7") (pinfunction "Q7_7") (pintype "passive"))
    )
    (net (code "34") (name "/R_0") (class "Default")
      (node (ref "L1") (pin "1") (pinfunction "R_1") (pintype "passive"))
      (node (ref "R37") (pin "1") (pinfunction "1_1") (pintype "passive"))
    )
    (net (code "35") (name "/R_1") (class "Default")
      (node (ref "L2") (pin "1") (pinfunction "R_1") (pintype "passive"))
      (node (ref "R38") (pin "1") (pinfunction "1_1") (pintype "passive"))
    )
    (net (code "36") (name "/R_2") (class "Default")
      (node (ref "L3") (pin "1") (pinfunction "R_1") (pintype "passive"))
      (node (ref "R39") (pin "1") (pinfunction "1_1") (pintype "passive"))
    )
    (net (code "37") (name "/R_3") (class "Default")
      (node (ref "L4") (pin "1") (pinfunction "R_1") (pintype "passive"))
      (node (ref "R40") (pin "1") (pinfunction "1_1") (pintype "passive"))
    )
    (net (code "38") (name "/R_4") (class "Default")
      (node (ref "L5") (pin "1") (pinfunction "R_1") (pintype "passive"))
      (node (ref "R45") (pin "1") (pinfunction "1_1") (pintype "passive"))
    )
    (net (code "39") (name "/R_5") (class "Default")
      (node (ref "L6") (pin "1") (pinfunction "R_1") (pintype "passive"))
      (node (ref "R46") (pin "1") (pinfunction "1_1") (pintype "passive"))
    )
    (net (code "40") (name "/R_6") (class "Default")
      (node (ref "L7") (pin "1") (pinfunction "R_1") (pintype "passive"))
      (node (ref "R47") (pin "1") (pinfunction "1_1") (pintype "passive"))
    )
    (net (code "41") (name "/R_7") (class "Default")
      (node (ref "L8") (pin "1") (pinfunction "R_1") (pintype "passive"))
      (node (ref "R48") (pin "1") (pinfunction "1_1") (pintype "passive"))
    )
    (net (code "42") (name "/R_Q0") (class "Default")
      (node (ref "R33") (pin "1") (pinfunction "1_1") (pintype "passive"))
      (node (ref "SR3") (pin "15") (pinfunction "Q0_15") (pintype "passive"))
    )
    (net (code "43") (name "/R_Q1") (class "Default")
      (node (ref "R34") (pin "1") (pinfunction "1_1") (pintype "passive"))
      (node (ref "SR3") (pin "1") (pinfunction "Q1_1") (pintype "passive"))
    )
    (net (code "44") (name "/R_Q2") (class "Default")
      (node (ref "R35") (pin "1") (pinfunction "1_1") (pintype "passive"))
      (node (ref "SR3") (pin "2") (pinfunction "Q2_2") (pintype "passive"))
    )
    (net (code "45") (name "/R_Q3") (class "Default")
      (node (ref "R36") (pin "1") (pinfunction "1_1") (pintype "passive"))
      (node (ref "SR3") (pin "3") (pinfunction "Q3_3") (pintype "passive"))
    )
    (net (code "46") (name "/R_Q4") (class "Default")
      (node (ref "R41") (pin "1") (pinfunction "1_1") (pintype "passive"))
      (node (ref "SR3") (pin "4") (pinfunction "Q4_4") (pintype "passive"))
    )
    (net (code "47") (name "/R_Q5") (class "Default")
      (node (ref "R42") (pin "1") (pinfunction "1_1") (pintype "passive"))
      (node (ref "SR3") (pin "5") (pinfunction "Q5_5") (pintype "passive"))
    )
    (net (code "48") (name "/R_Q6") (class "Default")
      (node (ref "R43") (pin "1") (pinfunction "1_1") (pintype "passive"))
      (node (ref "SR3") (pin "6") (pinfunction "Q6_6") (pintype "passive"))
    )
    (net (code "49") (name "/R_Q7") (class "Default")
      (node (ref "R44") (pin "1") (pinfunction "1_1") (pintype "passive"))
      (node (ref "SR3") (pin "7") (pinfunction "Q7_7") (pintype "passive"))
    )
    (net (code "50") (name "/SHCP") (class "Default")
      (node (ref "P1") (pin "3") (pinfunction "3_3") (pintype "passive"))
      (node (ref "P2") (pin "3") (pinfunction "3_3") (pintype "passive"))
      (node (ref "SR1") (pin "11") (pinfunction "SHCP_11") (pintype "passive"))
      (node (ref "SR2") (pin "11") (pinfunction "SHCP_11") (pintype "passive"))
      (node (ref "SR3") (pin "11") (pinfunction "SHCP_11") (pintype "passive"))
    )
    (net (code "51") (name "/STP") (class "Default")
      (node (ref "P1") (pin "2") (pinfunction "2_2") (pintype "passive"))
      (node (ref "P2") (pin "2") (pinfunction "2_2") (pintype "passive"))
      (node (ref "SR1") (pin "12") (pinfunction "STP_12") (pintype "passive"))
      (node (ref "SR2") (pin "12") (pinfunction "STP_12") (pintype "passive"))
      (node (ref "SR3") (pin "12") (pinfunction "STP_12") (pintype "passive"))
    )
    (net (code "52") (name "/SerialIn") (class "Default")
      (node (ref "P1") (pin "4") (pinfunction "4_4") (pintype "passive"))
      (node (ref "SR1") (pin "14") (pinfunction "DS_14") (pintype "passive"))
    )
    (net (code "53") (name "/SerialOut") (class "Default")
      (node (ref "P2") (pin "4") (pinfunction "4_4") (pintype "passive"))
      (node (ref "SR3") (pin "9") (pinfunction "Q7S_9") (pintype "passive"))
    )
    (net (code "54") (name "5V") (class "Default")
      (node (ref "C1") (pin "1") (pinfunction "1_1") (pintype "passive"))
      (node (ref "C2") (pin "1") (pinfunction "1_1") (pintype "passive"))
      (node (ref "C3") (pin "1") (pinfunction "1_1") (pintype "passive"))
      (node (ref "C4") (pin "1") (pinfunction "1_1") (pintype "passive"))
      (node (ref "C5") (pin "1") (pinfunction "1_1") (pintype "passive"))
      (node (ref "C6") (pin "1") (pinfunction "1_1") (pintype "passive"))
      (node (ref "P1") (pin "1") (pinfunction "1_1") (pintype "passive"))
      (node (ref "P2") (pin "1") (pinfunction "1_1") (pintype "passive"))
      (node (ref "SR1") (pin "10") (pinfunction "MR_10") (pintype "passive"))
      (node (ref "SR1") (pin "16") (pinfunction "VCC_16") (pintype "passive"))
      (node (ref "SR2") (pin "10") (pinfunction "MR_10") (pintype "passive"))
      (node (ref "SR2") (pin "16") (pinfunction "VCC_16") (pintype "passive"))
      (node (ref "SR3") (pin "10") (pinfunction "MR_10") (pintype "passive"))
      (node (ref "SR3") (pin "16") (pinfunction "VCC_16") (pintype "passive"))
      (node (ref "T1") (pin "2") (pinfunction "Collector_2") (pintype "passive"))
      (node (ref "T10") (pin "2") (pinfunction "Collector_2") (pintype "passive"))
      (node (ref "T11") (pin "2") (pinfunction "Collector_2") (pintype "passive"))
      (node (ref "T12") (pin "2") (pinfunction "Collector_2") (pintype "passive"))
      (node (ref "T13") (pin "2") (pinfunction "Collector_2") (pintype "passive"))
      (node (ref "T14") (pin "2") (pinfunction "Collector_2") (pintype "passive"))
      (node (ref "T15") (pin "2") (pinfunction "Collector_2") (pintype "passive"))
      (node (ref "T16") (pin "2") (pinfunction "Collector_2") (pintype "passive"))
      (node (ref "T17") (pin "2") (pinfunction "Collector_2") (pintype "passive"))
      (node (ref "T18") (pin "2") (pinfunction "Collector_2") (pintype "passive"))
      (node (ref "T19") (pin "2") (pinfunction "Collector_2") (pintype "passive"))
      (node (ref "T2") (pin "2") (pinfunction "Collector_2") (pintype "passive"))
      (node (ref "T20") (pin "2") (pinfunction "Collector_2") (pintype "passive"))
      (node (ref "T21") (pin "2") (pinfunction "Collector_2") (pintype "passive"))
      (node (ref "T22") (pin "2") (pinfunction "Collector_2") (pintype "passive"))
      (node (ref "T23") (pin "2") (pinfunction "Collector_2") (pintype "passive"))
      (node (ref "T24") (pin "2") (pinfunction "Collector_2") (pintype "passive"))
      (node (ref "T3") (pin "2") (pinfunction "Collector_2") (pintype "passive"))
      (node (ref "T4") (pin "2") (pinfunction "Collector_2") (pintype "passive"))
      (node (ref "T5") (pin "2") (pinfunction "Collector_2") (pintype "passive"))
      (node (ref "T6") (pin "2") (pinfunction "Collector_2") (pintype "passive"))
      (node (ref "T7") (pin "2") (pinfunction "Collector_2") (pintype "passive"))
      (node (ref "T8") (pin "2") (pinfunction "Collector_2") (pintype "passive"))
      (node (ref "T9") (pin "2") (pinfunction "Collector_2") (pintype "passive"))
    )
    (net (code "55") (name "GND") (class "Default")
      (node (ref "C1") (pin "2") (pinfunction "2_2") (pintype "passive"))
      (node (ref "C2") (pin "2") (pinfunction "2_2") (pintype "passive"))
      (node (ref "C3") (pin "2") (pinfunction "2_2") (pintype "passive"))
      (node (ref "C4") (pin "2") (pinfunction "2_2") (pintype "passive"))
      (node (ref "C5") (pin "2") (pinfunction "2_2") (pintype "passive"))
      (node (ref "C6") (pin "2") (pinfunction "2_2") (pintype "passive"))
      (node (ref "P1") (pin "5") (pinfunction "5_5") (pintype "passive"))
      (node (ref "P2") (pin "5") (pinfunction "5_5") (pintype "passive"))
      (node (ref "SR1") (pin "13") (pinfunction "OE_13") (pintype "passive"))
      (node (ref "SR1") (pin "8") (pinfunction "GND_8") (pintype "passive"))
      (node (ref "SR2") (pin "13") (pinfunction "OE_13") (pintype "passive"))
      (node (ref "SR2") (pin "8") (pinfunction "GND_8") (pintype "passive"))
      (node (ref "SR3") (pin "13") (pinfunction "OE_13") (pintype "passive"))
      (node (ref "SR3") (pin "8") (pinfunction "GND_8") (pintype "passive"))
    )
    (net (code "56") (name "Net-(SR1-Q7S)") (class "Default")
      (node (ref "SR1") (pin "9") (pinfunction "Q7S_9") (pintype "passive"))
      (node (ref "SR2") (pin "14") (pinfunction "DS_14") (pintype "passive"))
    )
    (net (code "57") (name "Net-(SR2-Q7S)") (class "Default")
      (node (ref "SR2") (pin "9") (pinfunction "Q7S_9") (pintype "passive"))
      (node (ref "SR3") (pin "14") (pinfunction "DS_14") (pintype "passive"))
    )
    (net (code "58") (name "Net-(T1-Base)") (class "Default")
      (node (ref "R1") (pin "2") (pinfunction "2_2") (pintype "passive"))
      (node (ref "T1") (pin "1") (pinfunction "Base_1") (pintype "passive"))
    )
    (net (code "59") (name "Net-(T1-Emitter)") (class "Default")
      (node (ref "R5") (pin "2") (pinfunction "2_2") (pintype "passive"))
      (node (ref "T1") (pin "3") (pinfunction "Emitter_3") (pintype "passive"))
    )
    (net (code "60") (name "Net-(T2-Base)") (class "Default")
      (node (ref "R2") (pin "2") (pinfunction "2_2") (pintype "passive"))
      (node (ref "T2") (pin "1") (pinfunction "Base_1") (pintype "passive"))
    )
    (net (code "61") (name "Net-(T2-Emitter)") (class "Default")
      (node (ref "R6") (pin "2") (pinfunction "2_2") (pintype "passive"))
      (node (ref "T2") (pin "3") (pinfunction "Emitter_3") (pintype "passive"))
    )
    (net (code "62") (name "Net-(T3-Base)") (class "Default")
      (node (ref "R3") (pin "2") (pinfunction "2_2") (pintype "passive"))
      (node (ref "T3") (pin "1") (pinfunction "Base_1") (pintype "passive"))
    )
    (net (code "63") (name "Net-(T3-Emitter)") (class "Default")
      (node (ref "R7") (pin "2") (pinfunction "2_2") (pintype "passive"))
      (node (ref "T3") (pin "3") (pinfunction "Emitter_3") (pintype "passive"))
    )
    (net (code "64") (name "Net-(T4-Base)") (class "Default")
      (node (ref "R4") (pin "2") (pinfunction "2_2") (pintype "passive"))
      (node (ref "T4") (pin "1") (pinfunction "Base_1") (pintype "passive"))
    )
    (net (code "65") (name "Net-(T4-Emitter)") (class "Default")
      (node (ref "R8") (pin "2") (pinfunction "2_2") (pintype "passive"))
      (node (ref "T4") (pin "3") (pinfunction "Emitter_3") (pintype "passive"))
    )
    (net (code "66") (name "Net-(T5-Base)") (class "Default")
      (node (ref "R9") (pin "2") (pinfunction "2_2") (pintype "passive"))
      (node (ref "T5") (pin "1") (pinfunction "Base_1") (pintype "passive"))
    )
    (net (code "67") (name "Net-(T5-Emitter)") (class "Default")
      (node (ref "R13") (pin "2") (pinfunction "2_2") (pintype "passive"))
      (node (ref "T5") (pin "3") (pinfunction "Emitter_3") (pintype "passive"))
    )
    (net (code "68") (name "Net-(T6-Base)") (class "Default")
      (node (ref "R10") (pin "2") (pinfunction "2_2") (pintype "passive"))
      (node (ref "T6") (pin "1") (pinfunction "Base_1") (pintype "passive"))
    )
    (net (code "69") (name "Net-(T6-Emitter)") (class "Default")
      (node (ref "R14") (pin "2") (pinfunction "2_2") (pintype "passive"))
      (node (ref "T6") (pin "3") (pinfunction "Emitter_3") (pintype "passive"))
    )
    (net (code "70") (name "Net-(T7-Base)") (class "Default")
      (node (ref "R11") (pin "2") (pinfunction "2_2") (pintype "passive"))
      (node (ref "T7") (pin "1") (pinfunction "Base_1") (pintype "passive"))
    )
    (net (code "71") (name "Net-(T7-Emitter)") (class "Default")
      (node (ref "R15") (pin "2") (pinfunction "2_2") (pintype "passive"))
      (node (ref "T7") (pin "3") (pinfunction "Emitter_3") (pintype "passive"))
    )
    (net (code "72") (name "Net-(T8-Base)") (class "Default")
      (node (ref "R12") (pin "2") (pinfunction "2_2") (pintype "passive"))
      (node (ref "T8") (pin "1") (pinfunction "Base_1") (pintype "passive"))
    )
    (net (code "73") (name "Net-(T8-Emitter)") (class "Default")
      (node (ref "R16") (pin "2") (pinfunction "2_2") (pintype "passive"))
      (node (ref "T8") (pin "3") (pinfunction "Emitter_3") (pintype "passive"))
    )
    (net (code "74") (name "Net-(T9-Base)") (class "Default")
      (node (ref "R17") (pin "2") (pinfunction "2_2") (pintype "passive"))
      (node (ref "T9") (pin "1") (pinfunction "Base_1") (pintype "passive"))
    )
    (net (code "75") (name "Net-(T9-Emitter)") (class "Default")
      (node (ref "R21") (pin "2") (pinfunction "2_2") (pintype "passive"))
      (node (ref "T9") (pin "3") (pinfunction "Emitter_3") (pintype "passive"))
    )
    (net (code "76") (name "Net-(T10-Base)") (class "Default")
      (node (ref "R18") (pin "2") (pinfunction "2_2") (pintype "passive"))
      (node (ref "T10") (pin "1") (pinfunction "Base_1") (pintype "passive"))
    )
    (net (code "77") (name "Net-(T10-Emitter)") (class "Default")
      (node (ref "R22") (pin "2") (pinfunction "2_2") (pintype "passive"))
      (node (ref "T10") (pin "3") (pinfunction "Emitter_3") (pintype "passive"))
    )
    (net (code "78") (name "Net-(T11-Base)") (class "Default")
      (node (ref "R19") (pin "2") (pinfunction "2_2") (pintype "passive"))
      (node (ref "T11") (pin "1") (pinfunction "Base_1") (pintype "passive"))
    )
    (net (code "79") (name "Net-(T11-Emitter)") (class "Default")
      (node (ref "R23") (pin "2") (pinfunction "2_2") (pintype "passive"))
      (node (ref "T11") (pin "3") (pinfunction "Emitter_3") (pintype "passive"))
    )
    (net (code "80") (name "Net-(T12-Base)") (class "Default")
      (node (ref "R20") (pin "2") (pinfunction "2_2") (pintype "passive"))
      (node (ref "T12") (pin "1") (pinfunction "Base_1") (pintype "passive"))
    )
    (net (code "81") (name "Net-(T12-Emitter)") (class "Default")
      (node (ref "R24") (pin "2") (pinfunction "2_2") (pintype "passive"))
      (node (ref "T12") (pin "3") (pinfunction "Emitter_3") (pintype "passive"))
    )
    (net (code "82") (name "Net-(T13-Base)") (class "Default")
      (node (ref "R25") (pin "2") (pinfunction "2_2") (pintype "passive"))
      (node (ref "T13") (pin "1") (pinfunction "Base_1") (pintype "passive"))
    )
    (net (code "83") (name "Net-(T13-Emitter)") (class "Default")
      (node (ref "R29") (pin "2") (pinfunction "2_2") (pintype "passive"))
      (node (ref "T13") (pin "3") (pinfunction "Emitter_3") (pintype "passive"))
    )
    (net (code "84") (name "Net-(T14-Base)") (class "Default")
      (node (ref "R26") (pin "2") (pinfunction "2_2") (pintype "passive"))
      (node (ref "T14") (pin "1") (pinfunction "Base_1") (pintype "passive"))
    )
    (net (code "85") (name "Net-(T14-Emitter)") (class "Default")
      (node (ref "R30") (pin "2") (pinfunction "2_2") (pintype "passive"))
      (node (ref "T14") (pin "3") (pinfunction "Emitter_3") (pintype "passive"))
    )
    (net (code "86") (name "Net-(T15-Base)") (class "Default")
      (node (ref "R27") (pin "2") (pinfunction "2_2") (pintype "passive"))
      (node (ref "T15") (pin "1") (pinfunction "Base_1") (pintype "passive"))
    )
    (net (code "87") (name "Net-(T15-Emitter)") (class "Default")
      (node (ref "R31") (pin "2") (pinfunction "2_2") (pintype "passive"))
      (node (ref "T15") (pin "3") (pinfunction "Emitter_3") (pintype "passive"))
    )
    (net (code "88") (name "Net-(T16-Base)") (class "Default")
      (node (ref "R28") (pin "2") (pinfunction "2_2") (pintype "passive"))
      (node (ref "T16") (pin "1") (pinfunction "Base_1") (pintype "passive"))
    )
    (net (code "89") (name "Net-(T16-Emitter)") (class "Default")
      (node (ref "R32") (pin "2") (pinfunction "2_2") (pintype "passive"))
      (node (ref "T16") (pin "3") (pinfunction "Emitter_3") (pintype "passive"))
    )
    (net (code "90") (name "Net-(T17-Base)") (class "Default")
      (node (ref "R33") (pin "2") (pinfunction "2_2") (pintype "passive"))
      (node (ref "T17") (pin "1") (pinfunction "Base_1") (pintype "passive"))
    )
    (net (code "91") (name "Net-(T17-Emitter)") (class "Default")
      (node (ref "R37") (pin "2") (pinfunction "2_2") (pintype "passive"))
      (node (ref "T17") (pin "3") (pinfunction "Emitter_3") (pintype "passive"))
    )
    (net (code "92") (name "Net-(T18-Base)") (class "Default")
      (node (ref "R34") (pin "2") (pinfunction "2_2") (pintype "passive"))
      (node (ref "T18") (pin "1") (pinfunction "Base_1") (pintype "passive"))
    )
    (net (code "93") (name "Net-(T18-Emitter)") (class "Default")
      (node (ref "R38") (pin "2") (pinfunction "2_2") (pintype "passive"))
      (node (ref "T18") (pin "3") (pinfunction "Emitter_3") (pintype "passive"))
    )
    (net (code "94") (name "Net-(T19-Base)") (class "Default")
      (node (ref "R35") (pin "2") (pinfunction "2_2") (pintype "passive"))
      (node (ref "T19") (pin "1") (pinfunction "Base_1") (pintype "passive"))
    )
    (net (code "95") (name "Net-(T19-Emitter)") (class "Default")
      (node (ref "R39") (pin "2") (pinfunction "2_2") (pintype "passive"))
      (node (ref "T19") (pin "3") (pinfunction "Emitter_3") (pintype "passive"))
    )
    (net (code "96") (name "Net-(T20-Base)") (class "Default")
      (node (ref "R36") (pin "2") (pinfunction "2_2") (pintype "passive"))
      (node (ref "T20") (pin "1") (pinfunction "Base_1") (pintype "passive"))
    )
    (net (code "97") (name "Net-(T20-Emitter)") (class "Default")
      (node (ref "R40") (pin "2") (pinfunction "2_2") (pintype "passive"))
      (node (ref "T20") (pin "3") (pinfunction "Emitter_3") (pintype "passive"))
    )
    (net (code "98") (name "Net-(T21-Base)") (class "Default")
      (node (ref "R41") (pin "2") (pinfunction "2_2") (pintype "passive"))
      (node (ref "T21") (pin "1") (pinfunction "Base_1") (pintype "passive"))
    )
    (net (code "99") (name "Net-(T21-Emitter)") (class "Default")
      (node (ref "R45") (pin "2") (pinfunction "2_2") (pintype "passive"))
      (node (ref "T21") (pin "3") (pinfunction "Emitter_3") (pintype "passive"))
    )
    (net (code "100") (name "Net-(T22-Base)") (class "Default")
      (node (ref "R42") (pin "2") (pinfunction "2_2") (pintype "passive"))
      (node (ref "T22") (pin "1") (pinfunction "Base_1") (pintype "passive"))
    )
    (net (code "101") (name "Net-(T22-Emitter)") (class "Default")
      (node (ref "R46") (pin "2") (pinfunction "2_2") (pintype "passive"))
      (node (ref "T22") (pin "3") (pinfunction "Emitter_3") (pintype "passive"))
    )
    (net (code "102") (name "Net-(T23-Base)") (class "Default")
      (node (ref "R43") (pin "2") (pinfunction "2_2") (pintype "passive"))
      (node (ref "T23") (pin "1") (pinfunction "Base_1") (pintype "passive"))
    )
    (net (code "103") (name "Net-(T23-Emitter)") (class "Default")
      (node (ref "R47") (pin "2") (pinfunction "2_2") (pintype "passive"))
      (node (ref "T23") (pin "3") (pinfunction "Emitter_3") (pintype "passive"))
    )
    (net (code "104") (name "Net-(T24-Base)") (class "Default")
      (node (ref "R44") (pin "2") (pinfunction "2_2") (pintype "passive"))
      (node (ref "T24") (pin "1") (pinfunction "Base_1") (pintype "passive"))
    )
    (net (code "105") (name "Net-(T24-Emitter)") (class "Default")
      (node (ref "R48") (pin "2") (pinfunction "2_2") (pintype "passive"))
      (node (ref "T24") (pin "3") (pinfunction "Emitter_3") (pintype "passive"))
    )
  )
)
